# RS485_Demo_Bord_v1_0.net
KiCad netlist of a schematic drawn in Altium Designer
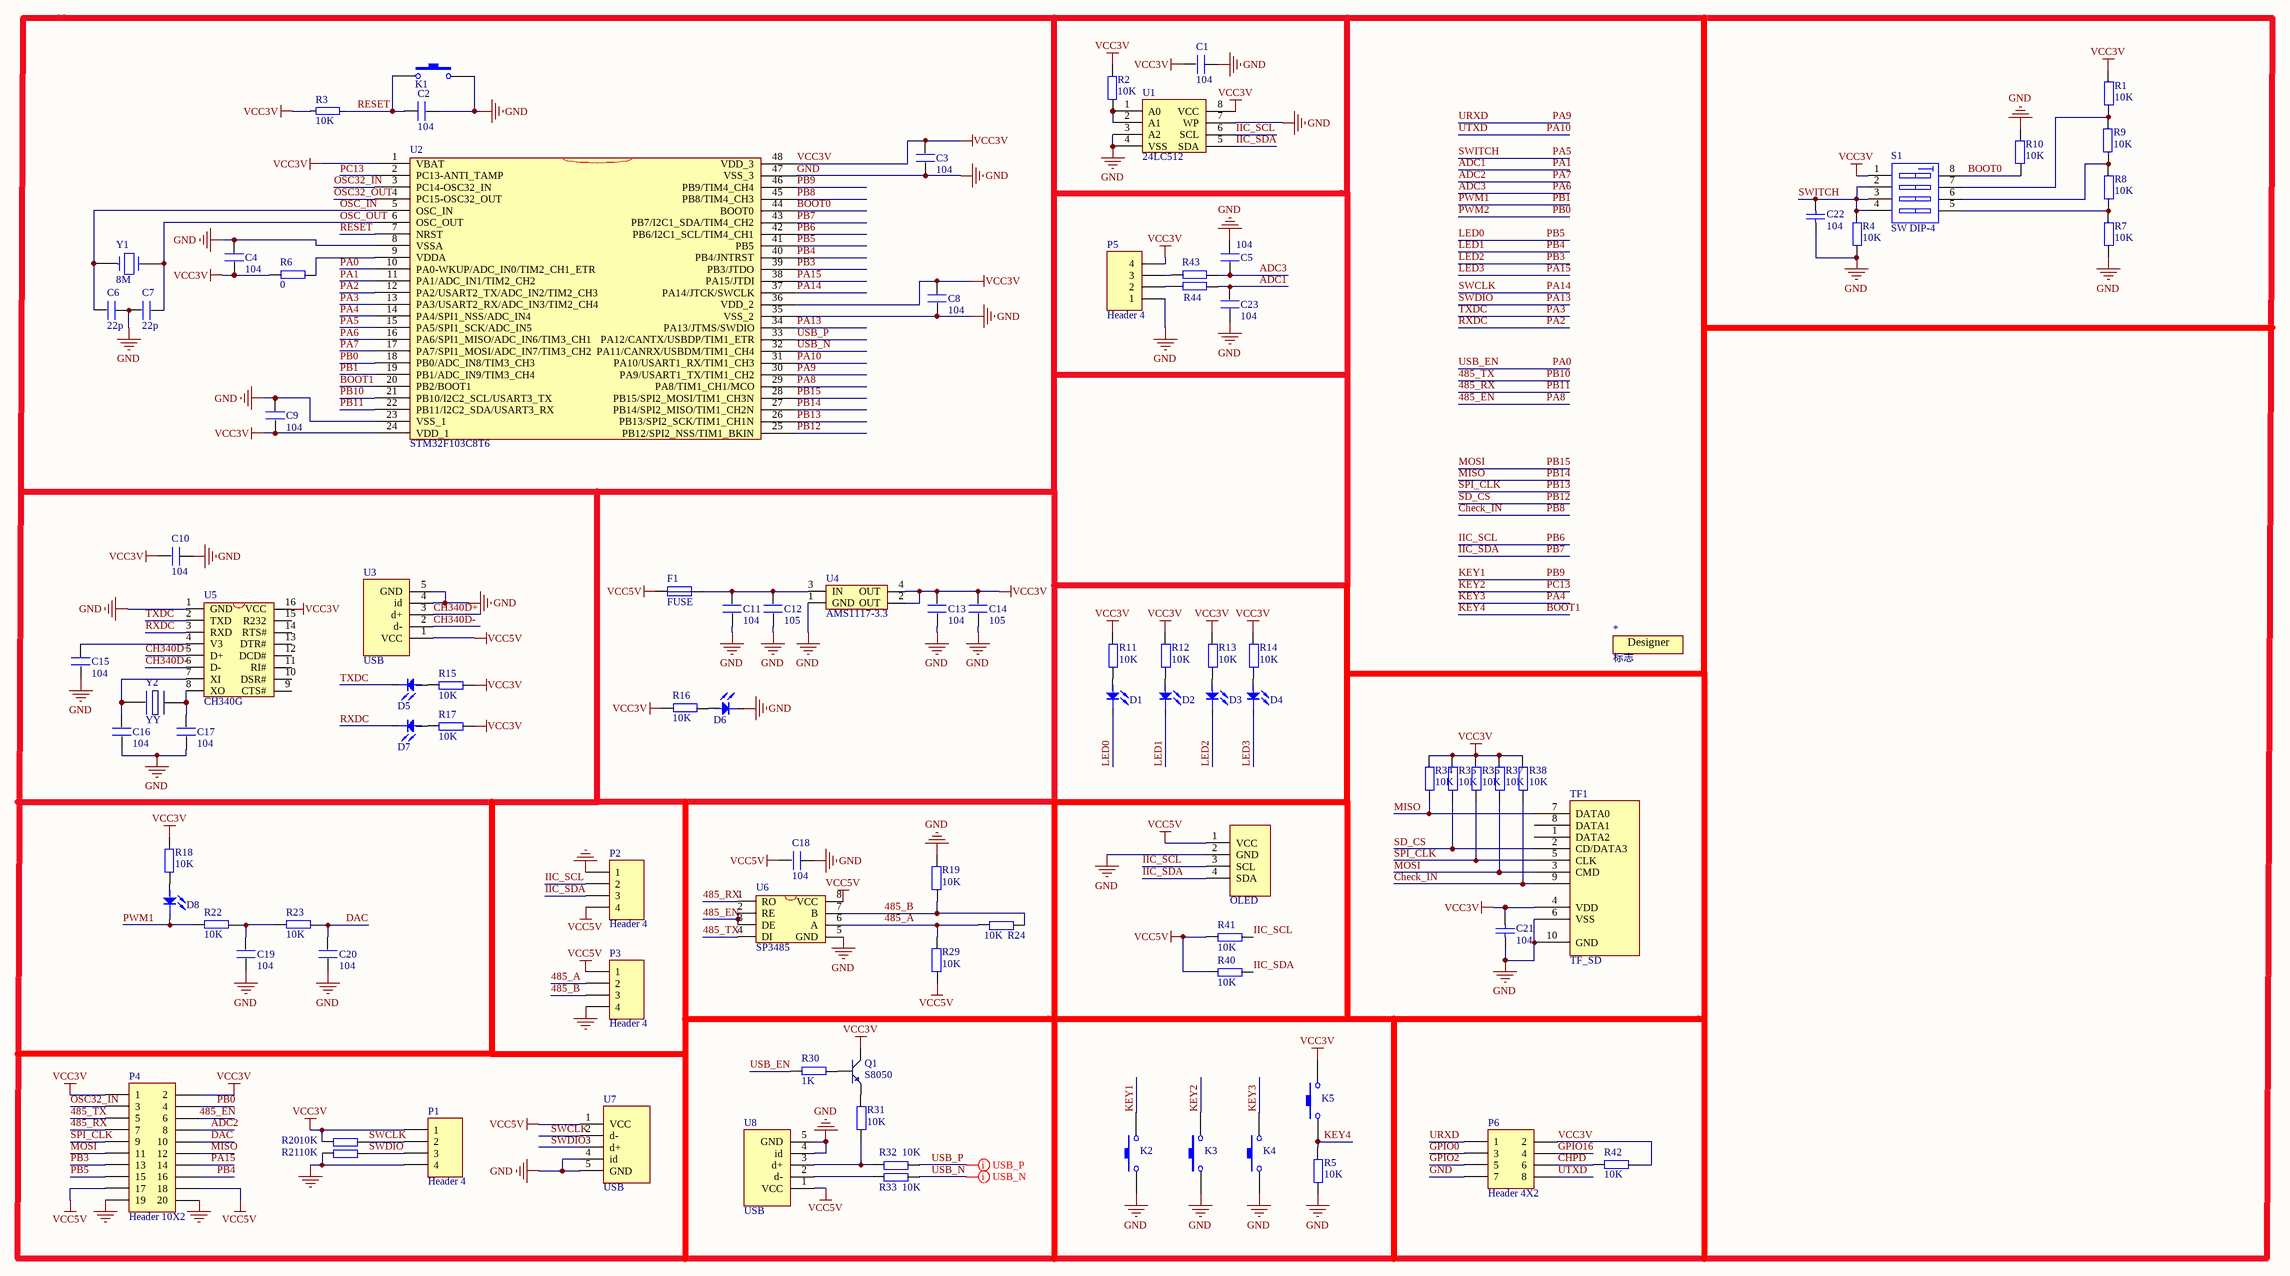
[diagram p0: RS485_Demo_Bord_v1.0.SchDoc]

(export (version "E")
  (design (tool "Eeschema 10.0.6"))
  (components
    (comp (ref "*") (value "标志") (footprint "Designer - 1") (libsource (lib "Mylib") (part "标志")))
    (comp (ref "C1") (value "104") (footprint "C_0805") (libsource (lib "Mylib") (part "C")))
    (comp (ref "C2") (value "104") (footprint "C_0805") (libsource (lib "Mylib") (part "C")))
    (comp (ref "C3") (value "104") (footprint "C_0805") (libsource (lib "Mylib") (part "C")))
    (comp (ref "C4") (value "104") (footprint "C_0805") (libsource (lib "Mylib") (part "C")))
    (comp (ref "C5") (value "104") (footprint "C_0805") (libsource (lib "Mylib") (part "C")))
    (comp (ref "C6") (value "22p") (footprint "C_0805") (libsource (lib "Mylib") (part "C")))
    (comp (ref "C7") (value "22p") (footprint "C_0805") (libsource (lib "Mylib") (part "C")))
    (comp (ref "C8") (value "104") (footprint "C_0805") (libsource (lib "Mylib") (part "C")))
    (comp (ref "C9") (value "104") (footprint "C_0805") (libsource (lib "Mylib") (part "C")))
    (comp (ref "C10") (value "104") (footprint "C_0805") (libsource (lib "Mylib") (part "C")))
    (comp (ref "C11") (value "104") (footprint "C_0805") (libsource (lib "Mylib") (part "C")))
    (comp (ref "C12") (value "105") (footprint "C_0805") (libsource (lib "Mylib") (part "C")))
    (comp (ref "C13") (value "104") (footprint "C_0805") (libsource (lib "Mylib") (part "C")))
    (comp (ref "C14") (value "105") (footprint "C_0805") (libsource (lib "Mylib") (part "C")))
    (comp (ref "C15") (value "104") (footprint "C_0805") (libsource (lib "Mylib") (part "C")))
    (comp (ref "C16") (value "104") (footprint "C_0805") (libsource (lib "Mylib") (part "C")))
    (comp (ref "C17") (value "104") (footprint "C_0805") (libsource (lib "Mylib") (part "C")))
    (comp (ref "C18") (value "104") (footprint "C_0805") (libsource (lib "Mylib") (part "C")))
    (comp (ref "C19") (value "104") (footprint "C_0805") (libsource (lib "Mylib") (part "C")))
    (comp (ref "C20") (value "104") (footprint "C_0805") (libsource (lib "Mylib") (part "C")))
    (comp (ref "C21")
      (value "104")
      (footprint "0805C")
      (description "Capacitor")
      (fields (field (name "PUBLISHER") "Altium Limited"))
      (libsource (lib "STM32F407VET6mini最小系统-原理图库") (part "Cap"))
    )
    (comp (ref "C22")
      (value "104")
      (footprint "0805C")
      (description "Capacitor")
      (fields (field (name "PUBLISHER") "Altium Limited"))
      (libsource (lib "STM32F407VET6mini最小系统-原理图库") (part "Cap"))
    )
    (comp (ref "C23") (value "104") (footprint "C_0805") (libsource (lib "Mylib") (part "C")))
    (comp (ref "D1") (value "LED") (footprint "0805-LED-RED") (libsource (lib "MY SCH LIB") (part "LED")))
    (comp (ref "D2") (value "LED") (footprint "0805-LED-RED") (libsource (lib "MY SCH LIB") (part "LED")))
    (comp (ref "D3") (value "LED") (footprint "0805-LED-RED") (libsource (lib "MY SCH LIB") (part "LED")))
    (comp (ref "D4") (value "LED") (footprint "0805-LED-RED") (libsource (lib "MY SCH LIB") (part "LED")))
    (comp (ref "D5") (value "LED") (footprint "0805-LED-RED") (libsource (lib "MY SCH LIB") (part "LED")))
    (comp (ref "D6") (value "LED") (footprint "0805-LED-RED") (libsource (lib "MY SCH LIB") (part "LED")))
    (comp (ref "D7") (value "LED") (footprint "0805-LED-RED") (libsource (lib "MY SCH LIB") (part "LED")))
    (comp (ref "D8") (value "LED") (footprint "0805-LED-RED") (libsource (lib "MY SCH LIB") (part "LED")))
    (comp (ref "F1") (value "FUSE") (footprint "0805") (libsource (lib "Mylib") (part "FUSE")))
    (comp (ref "K1") (value "KEY") (footprint "KEY_6") (libsource (lib "MY SCH LIB") (part "KEY")))
    (comp (ref "K2") (value "KEY") (footprint "KEY_6") (libsource (lib "MY SCH LIB") (part "KEY")))
    (comp (ref "K3") (value "KEY") (footprint "KEY_6") (libsource (lib "MY SCH LIB") (part "KEY")))
    (comp (ref "K4") (value "KEY") (footprint "KEY_6") (libsource (lib "MY SCH LIB") (part "KEY")))
    (comp (ref "K5") (value "KEY") (footprint "KEY_6") (libsource (lib "MY SCH LIB") (part "KEY")))
    (comp (ref "OLED")
      (value "OLED")
      (footprint "OLED__IIC_1")
      (libsource (lib "MY SCH LIB") (part "OLED_IIC_1"))
    )
    (comp (ref "P1")
      (value "Header 4")
      (footprint "XH_4_V")
      (description "Header, 4-Pin")
      (fields (field (name "PUBLISHER") "Altium Limited"))
      (libsource (lib "") (part "Header 4_1"))
    )
    (comp (ref "P2")
      (value "Header 4")
      (footprint "XH_4_V")
      (description "Header, 4-Pin")
      (fields (field (name "PUBLISHER") "Altium Limited"))
      (libsource (lib "") (part "Header 4_1"))
    )
    (comp (ref "P3")
      (value "Header 4")
      (footprint "XH_4_V")
      (description "Header, 4-Pin")
      (fields (field (name "PUBLISHER") "Altium Limited"))
      (libsource (lib "") (part "Header 4_1"))
    )
    (comp (ref "P4")
      (value "Header 10X2")
      (footprint "JTAG_20 - E")
      (description "Header, 10-Pin, Dual row")
      (fields (field (name "PUBLISHER") "Altium Limited"))
      (libsource (lib "接口插座") (part "Header 10X2"))
    )
    (comp (ref "P5")
      (value "Header 4")
      (footprint "XH_4_V")
      (description "Header, 4-Pin")
      (fields (field (name "PUBLISHER") "Altium Limited"))
      (libsource (lib "接口插座") (part "Header 4"))
    )
    (comp (ref "P6")
      (value "Header 4X2")
      (footprint "HDR2X4")
      (description "Header, 4-Pin, Dual row")
      (fields (field (name "PUBLISHER") "Altium Limited"))
      (libsource (lib "接口插座") (part "Header 4X2"))
    )
    (comp (ref "Q1") (value "S8050") (footprint "SOT23-3") (libsource (lib "Mylib") (part "NPN")))
    (comp (ref "R1") (value "10K") (footprint "0805") (libsource (lib "Mylib") (part "R")))
    (comp (ref "R2") (value "10K") (footprint "0805") (libsource (lib "Mylib") (part "R")))
    (comp (ref "R3") (value "10K") (footprint "0805") (libsource (lib "电阻") (part "RES")))
    (comp (ref "R4") (value "10K") (footprint "0805") (libsource (lib "Mylib") (part "R")))
    (comp (ref "R5") (value "10K") (footprint "0805") (libsource (lib "Mylib") (part "R")))
    (comp (ref "R6") (value "0") (footprint "0805") (libsource (lib "Mylib") (part "R")))
    (comp (ref "R7") (value "10K") (footprint "0805") (libsource (lib "Mylib") (part "R")))
    (comp (ref "R8") (value "10K") (footprint "0805") (libsource (lib "Mylib") (part "R")))
    (comp (ref "R9") (value "10K") (footprint "0805") (libsource (lib "Mylib") (part "R")))
    (comp (ref "R10") (value "10K") (footprint "0805") (libsource (lib "Mylib") (part "R")))
    (comp (ref "R11") (value "10K") (footprint "0805") (libsource (lib "Mylib") (part "R")))
    (comp (ref "R12") (value "10K") (footprint "0805") (libsource (lib "Mylib") (part "R")))
    (comp (ref "R13") (value "10K") (footprint "0805") (libsource (lib "Mylib") (part "R")))
    (comp (ref "R14") (value "10K") (footprint "0805") (libsource (lib "Mylib") (part "R")))
    (comp (ref "R15") (value "10K") (footprint "0805") (libsource (lib "Mylib") (part "R")))
    (comp (ref "R16") (value "10K") (footprint "0805") (libsource (lib "Mylib") (part "R")))
    (comp (ref "R17") (value "10K") (footprint "0805") (libsource (lib "Mylib") (part "R")))
    (comp (ref "R18") (value "10K") (footprint "0805") (libsource (lib "Mylib") (part "R")))
    (comp (ref "R19") (value "10K") (footprint "0805") (libsource (lib "Mylib") (part "R")))
    (comp (ref "R20") (value "10K") (footprint "0805") (libsource (lib "Mylib") (part "R")))
    (comp (ref "R21") (value "10K") (footprint "0805") (libsource (lib "Mylib") (part "R")))
    (comp (ref "R22") (value "10K") (footprint "0805") (libsource (lib "Mylib") (part "R")))
    (comp (ref "R23") (value "10K") (footprint "0805") (libsource (lib "Mylib") (part "R")))
    (comp (ref "R24") (value "10K") (footprint "0805") (libsource (lib "Mylib") (part "R")))
    (comp (ref "R29") (value "10K") (footprint "0805") (libsource (lib "Mylib") (part "R")))
    (comp (ref "R30") (value "1K") (footprint "0805") (libsource (lib "Mylib") (part "R")))
    (comp (ref "R31") (value "10K") (footprint "0805") (libsource (lib "Mylib") (part "R")))
    (comp (ref "R32") (value "10K") (footprint "0805") (libsource (lib "Mylib") (part "R")))
    (comp (ref "R33") (value "10K") (footprint "0805") (libsource (lib "Mylib") (part "R")))
    (comp (ref "R34") (value "10K") (footprint "0805") (libsource (lib "Mylib") (part "R")))
    (comp (ref "R35") (value "10K") (footprint "0805") (libsource (lib "Mylib") (part "R")))
    (comp (ref "R36") (value "10K") (footprint "0805") (libsource (lib "Mylib") (part "R")))
    (comp (ref "R37") (value "10K") (footprint "0805") (libsource (lib "Mylib") (part "R")))
    (comp (ref "R38") (value "10K") (footprint "0805") (libsource (lib "Mylib") (part "R")))
    (comp (ref "R40") (value "10K") (footprint "0805") (libsource (lib "Mylib") (part "R")))
    (comp (ref "R41") (value "10K") (footprint "0805") (libsource (lib "Mylib") (part "R")))
    (comp (ref "R42") (value "10K") (footprint "0805") (libsource (lib "Mylib") (part "R")))
    (comp (ref "R43") (value "10K") (footprint "0805") (libsource (lib "Mylib") (part "R")))
    (comp (ref "R44") (value "10K") (footprint "0805") (libsource (lib "Mylib") (part "R")))
    (comp (ref "S1")
      (value "SW DIP-4")
      (footprint "SWITCH_DIP-4")
      (description "DIP Switch")
      (libsource (lib "MY SCH LIB") (part "SW DIP-4"))
    )
    (comp (ref "TF1") (value "TF_SD") (footprint "TF_SD") (libsource (lib "stm32f103vet6") (part "TF_SD")))
    (comp (ref "U1") (value "24LC512") (footprint "SO-8") (libsource (lib "Mylib") (part "24LC512")))
    (comp (ref "U2")
      (value "STM32F103C8T6")
      (footprint "LQFP-48_M")
      (libsource (lib "stm32") (part "STM32F103C6"))
    )
    (comp (ref "U3") (value "USB") (footprint "USB_MICRO_F") (libsource (lib "") (part "USB_1")))
    (comp (ref "U4")
      (value "AMS1117-3.3")
      (footprint "SOT223")
      (libsource (lib "MY SCH LIB") (part "AMS1117"))
    )
    (comp (ref "U5") (value "CH340G") (footprint "SO-16") (libsource (lib "Mylib") (part "CH340G")))
    (comp (ref "U6")
      (value "SP3485")
      (footprint "SOP-8")
      (libsource (lib "战舰STM32开发板底板封装库") (part "MAX3485"))
    )
    (comp (ref "U7") (value "USB") (footprint "USB_MICRO_F") (libsource (lib "MY SCH LIB") (part "USB")))
    (comp (ref "U8") (value "USB") (footprint "USB_MICRO_F") (libsource (lib "") (part "USB_1")))
    (comp (ref "Y1")
      (value "8M")
      (footprint "XTAL-3")
      (description "Crystal")
      (libsource (lib "MY SCH LIB") (part "CRYSTAL"))
    )
    (comp (ref "Y2") (value "YY") (footprint "XTAL-3") (libsource (lib "Mylib") (part "YY")))
  )
  (nets
    (net (code "1") (name "/485_A") (class "Default")
      (node (ref "P3") (pin "2") (pinfunction "2_2") (pintype "passive"))
      (node (ref "R24") (pin "1") (pintype "passive"))
      (node (ref "R29") (pin "1") (pintype "passive"))
      (node (ref "U6") (pin "6") (pinfunction "A_6") (pintype "passive"))
    )
    (net (code "2") (name "/485_B") (class "Default")
      (node (ref "P3") (pin "3") (pinfunction "3_3") (pintype "passive"))
      (node (ref "R19") (pin "2") (pintype "passive"))
      (node (ref "R24") (pin "2") (pintype "passive"))
      (node (ref "U6") (pin "7") (pinfunction "B_7") (pintype "passive"))
    )
    (net (code "3") (name "/485_EN") (class "Default")
      (node (ref "P4") (pin "6") (pinfunction "6_6") (pintype "passive"))
      (node (ref "U2") (pin "29") (pinfunction "PA8/TIM1_CH1/MCO_29") (pintype "passive"))
      (node (ref "U6") (pin "2") (pinfunction "RE_2") (pintype "passive"))
      (node (ref "U6") (pin "3") (pinfunction "DE_3") (pintype "passive"))
    )
    (net (code "4") (name "/485_RX") (class "Default")
      (node (ref "P4") (pin "7") (pinfunction "7_7") (pintype "passive"))
      (node (ref "U2") (pin "22") (pinfunction "PB11/I2C2_SDA/USART3_RX_22") (pintype "passive"))
      (node (ref "U6") (pin "1") (pinfunction "RO_1") (pintype "passive"))
    )
    (net (code "5") (name "/485_TX") (class "Default")
      (node (ref "P4") (pin "5") (pinfunction "5_5") (pintype "passive"))
      (node (ref "U2") (pin "21") (pinfunction "PB10/I2C2_SCL/USART3_TX_21") (pintype "passive"))
      (node (ref "U6") (pin "4") (pinfunction "DI_4") (pintype "passive"))
    )
    (net (code "6") (name "/ADC1") (class "Default")
      (node (ref "C23") (pin "2") (pintype "passive"))
      (node (ref "R44") (pin "1") (pintype "passive"))
      (node (ref "U2") (pin "11") (pinfunction "PA1/ADC_IN1/TIM2_CH2_11") (pintype "passive"))
    )
    (net (code "7") (name "/ADC2") (class "Default")
      (node (ref "P4") (pin "8") (pinfunction "8_8") (pintype "passive"))
      (node (ref "U2") (pin "17") (pinfunction "PA7/SPI1_MOSI/ADC_IN7/TIM3_CH2_17") (pintype "passive"))
    )
    (net (code "8") (name "/ADC3") (class "Default")
      (node (ref "C5") (pin "1") (pintype "passive"))
      (node (ref "R43") (pin "1") (pintype "passive"))
      (node (ref "U2") (pin "16") (pinfunction "PA6/SPI1_MISO/ADC_IN6/TIM3_CH1_16") (pintype "passive"))
    )
    (net (code "9") (name "/BOOT0") (class "Default")
      (node (ref "R10") (pin "2") (pintype "passive"))
      (node (ref "S1") (pin "8") (pinfunction "B1_8") (pintype "passive"))
      (node (ref "U2") (pin "44") (pinfunction "BOOT0_44") (pintype "passive"))
    )
    (net (code "10") (name "/BOOT1") (class "Default")
      (node (ref "K5") (pin "1") (pinfunction "1_1") (pintype "passive"))
      (node (ref "R5") (pin "2") (pintype "passive"))
      (node (ref "U2") (pin "20") (pinfunction "PB2/BOOT1_20") (pintype "passive"))
    )
    (net (code "11") (name "/CH340D+") (class "Default")
      (node (ref "U3") (pin "3") (pinfunction "d+_3") (pintype "passive"))
      (node (ref "U5") (pin "5") (pinfunction "D+_5") (pintype "passive"))
    )
    (net (code "12") (name "/CH340D-") (class "Default")
      (node (ref "U3") (pin "2") (pinfunction "d-_2") (pintype "passive"))
      (node (ref "U5") (pin "6") (pinfunction "D-_6") (pintype "passive"))
    )
    (net (code "13") (name "/CHPD") (class "Default")
      (node (ref "P6") (pin "6") (pinfunction "6_6") (pintype "passive"))
      (node (ref "R42") (pin "2") (pintype "passive"))
    )
    (net (code "14") (name "/Check_IN") (class "Default")
      (node (ref "R38") (pin "1") (pintype "passive"))
      (node (ref "TF1") (pin "9") (pinfunction "VSS_9") (pintype "passive"))
      (node (ref "U2") (pin "45") (pinfunction "PB8/TIM4_CH3_45") (pintype "passive"))
    )
    (net (code "15") (name "/DAC") (class "Default")
      (node (ref "C20") (pin "2") (pintype "passive"))
      (node (ref "P4") (pin "10") (pinfunction "10_10") (pintype "passive"))
      (node (ref "R23") (pin "1") (pintype "passive"))
    )
    (net (code "16") (name "/GPIO0") (class "Default")
      (node (ref "P6") (pin "3") (pinfunction "3_3") (pintype "passive"))
    )
    (net (code "17") (name "/GPIO2") (class "Default")
      (node (ref "P6") (pin "5") (pinfunction "5_5") (pintype "passive"))
    )
    (net (code "18") (name "/GPIO16") (class "Default")
      (node (ref "P6") (pin "4") (pinfunction "4_4") (pintype "passive"))
    )
    (net (code "19") (name "/IIC_SCL") (class "Default")
      (node (ref "OLED") (pin "3") (pinfunction "SCL_3") (pintype "passive"))
      (node (ref "P2") (pin "2") (pinfunction "2_2") (pintype "passive"))
      (node (ref "R41") (pin "2") (pintype "passive"))
      (node (ref "U1") (pin "6") (pinfunction "SCL_6") (pintype "passive"))
      (node (ref "U2") (pin "42") (pinfunction "PB6/I2C1_SCL/TIM4_CH1_42") (pintype "passive"))
    )
    (net (code "20") (name "/IIC_SDA") (class "Default")
      (node (ref "OLED") (pin "4") (pinfunction "SDA_4") (pintype "passive"))
      (node (ref "P2") (pin "3") (pinfunction "3_3") (pintype "passive"))
      (node (ref "R40") (pin "2") (pintype "passive"))
      (node (ref "U1") (pin "5") (pinfunction "SDA_5") (pintype "passive"))
      (node (ref "U2") (pin "43") (pinfunction "PB7/I2C1_SDA/TIM4_CH2_43") (pintype "passive"))
    )
    (net (code "21") (name "/KEY1") (class "Default")
      (node (ref "K2") (pin "2") (pinfunction "2_2") (pintype "passive"))
      (node (ref "U2") (pin "46") (pinfunction "PB9/TIM4_CH4_46") (pintype "passive"))
    )
    (net (code "22") (name "/KEY2") (class "Default")
      (node (ref "K3") (pin "2") (pinfunction "2_2") (pintype "passive"))
      (node (ref "U2") (pin "2") (pinfunction "PC13-ANTI_TAMP_2") (pintype "passive"))
    )
    (net (code "23") (name "/KEY3") (class "Default")
      (node (ref "K4") (pin "2") (pinfunction "2_2") (pintype "passive"))
      (node (ref "U2") (pin "14") (pinfunction "PA4/SPI1_NSS/ADC_IN4_14") (pintype "passive"))
    )
    (net (code "24") (name "/LED0") (class "Default")
      (node (ref "D1") (pin "K") (pintype "passive"))
      (node (ref "P4") (pin "15") (pinfunction "15_15") (pintype "passive"))
      (node (ref "U2") (pin "41") (pinfunction "PB5_41") (pintype "passive"))
    )
    (net (code "25") (name "/LED1") (class "Default")
      (node (ref "D2") (pin "K") (pintype "passive"))
      (node (ref "P4") (pin "16") (pinfunction "16_16") (pintype "passive"))
      (node (ref "U2") (pin "40") (pinfunction "PB4/JNTRST_40") (pintype "passive"))
    )
    (net (code "26") (name "/LED2") (class "Default")
      (node (ref "D3") (pin "K") (pintype "passive"))
      (node (ref "P4") (pin "13") (pinfunction "13_13") (pintype "passive"))
      (node (ref "U2") (pin "39") (pinfunction "PB3/JTDO_39") (pintype "passive"))
    )
    (net (code "27") (name "/LED3") (class "Default")
      (node (ref "D4") (pin "K") (pintype "passive"))
      (node (ref "P4") (pin "14") (pinfunction "14_14") (pintype "passive"))
      (node (ref "U2") (pin "38") (pinfunction "PA15/JTDI_38") (pintype "passive"))
    )
    (net (code "28") (name "/MISO") (class "Default")
      (node (ref "P4") (pin "12") (pinfunction "12_12") (pintype "passive"))
      (node (ref "R34") (pin "1") (pintype "passive"))
      (node (ref "TF1") (pin "7") (pinfunction "DATA0_7") (pintype "passive"))
      (node (ref "U2") (pin "27") (pinfunction "PB14/SPI2_MISO/TIM1_CH2N_27") (pintype "passive"))
    )
    (net (code "29") (name "/MOSI") (class "Default")
      (node (ref "P4") (pin "11") (pinfunction "11_11") (pintype "passive"))
      (node (ref "R37") (pin "1") (pintype "passive"))
      (node (ref "TF1") (pin "3") (pinfunction "CMD_3") (pintype "passive"))
      (node (ref "U2") (pin "28") (pinfunction "PB15/SPI2_MOSI/TIM1_CH3N_28") (pintype "passive"))
    )
    (net (code "30") (name "/OSC32_IN") (class "Default")
      (node (ref "P4") (pin "3") (pinfunction "3_3") (pintype "passive"))
      (node (ref "U2") (pin "3") (pinfunction "PC14-OSC32_IN_3") (pintype "passive"))
    )
    (net (code "31") (name "/OSC32_OUT") (class "Default")
      (node (ref "U2") (pin "4") (pinfunction "PC15-OSC32_OUT_4") (pintype "passive"))
    )
    (net (code "32") (name "/OSC_IN") (class "Default")
      (node (ref "C6") (pin "2") (pintype "passive"))
      (node (ref "U2") (pin "5") (pinfunction "OSC_IN_5") (pintype "passive"))
      (node (ref "Y1") (pin "1") (pinfunction "1_1") (pintype "passive"))
    )
    (net (code "33") (name "/OSC_OUT") (class "Default")
      (node (ref "C7") (pin "1") (pintype "passive"))
      (node (ref "U2") (pin "6") (pinfunction "OSC_OUT_6") (pintype "passive"))
      (node (ref "Y1") (pin "2") (pinfunction "2_2") (pintype "passive"))
    )
    (net (code "34") (name "/PA0") (class "Default")
      (node (ref "R30") (pin "2") (pintype "passive"))
      (node (ref "U2") (pin "10") (pinfunction "PA0-WKUP/ADC_IN0/TIM2_CH1_ETR_10") (pintype "passive"))
    )
    (net (code "35") (name "/PA2") (class "Default")
      (node (ref "D7") (pin "K") (pintype "passive"))
      (node (ref "U2") (pin "12") (pinfunction "PA2/USART2_TX/ADC_IN2/TIM2_CH3_12") (pintype "passive"))
      (node (ref "U5") (pin "3") (pinfunction "RXD_3") (pintype "passive"))
    )
    (net (code "36") (name "/PA3") (class "Default")
      (node (ref "D5") (pin "K") (pintype "passive"))
      (node (ref "U2") (pin "13") (pinfunction "PA3/USART2_RX/ADC_IN3/TIM2_CH4_13") (pintype "passive"))
      (node (ref "U5") (pin "2") (pinfunction "TXD_2") (pintype "passive"))
    )
    (net (code "37") (name "/PA5") (class "Default")
      (node (ref "C22") (pin "2") (pinfunction "2_2") (pintype "passive"))
      (node (ref "R4") (pin "2") (pintype "passive"))
      (node (ref "S1") (pin "2") (pinfunction "A2_2") (pintype "passive"))
      (node (ref "S1") (pin "3") (pinfunction "A3_3") (pintype "passive"))
      (node (ref "S1") (pin "4") (pinfunction "A4_4") (pintype "passive"))
      (node (ref "U2") (pin "15") (pinfunction "PA5/SPI1_SCK/ADC_IN5_15") (pintype "passive"))
    )
    (net (code "38") (name "/PA9") (class "Default")
      (node (ref "P6") (pin "1") (pinfunction "1_1") (pintype "passive"))
      (node (ref "U2") (pin "30") (pinfunction "PA9/USART1_TX/TIM1_CH2_30") (pintype "passive"))
    )
    (net (code "39") (name "/PA10") (class "Default")
      (node (ref "P6") (pin "8") (pinfunction "8_8") (pintype "passive"))
      (node (ref "U2") (pin "31") (pinfunction "PA10/USART1_RX/TIM1_CH3_31") (pintype "passive"))
    )
    (net (code "40") (name "/PA13") (class "Default")
      (node (ref "P1") (pin "3") (pinfunction "3_3") (pintype "passive"))
      (node (ref "R21") (pin "2") (pintype "passive"))
      (node (ref "U2") (pin "34") (pinfunction "PA13/JTMS/SWDIO_34") (pintype "passive"))
      (node (ref "U7") (pin "3") (pinfunction "d+_3") (pintype "passive"))
    )
    (net (code "41") (name "/PA14") (class "Default")
      (node (ref "P1") (pin "2") (pinfunction "2_2") (pintype "passive"))
      (node (ref "R20") (pin "2") (pintype "passive"))
      (node (ref "U2") (pin "37") (pinfunction "PA14/JTCK/SWCLK_37") (pintype "passive"))
      (node (ref "U7") (pin "2") (pinfunction "d-_2") (pintype "passive"))
    )
    (net (code "42") (name "/PB0") (class "Default")
      (node (ref "P4") (pin "4") (pinfunction "4_4") (pintype "passive"))
      (node (ref "U2") (pin "18") (pinfunction "PB0/ADC_IN8/TIM3_CH3_18") (pintype "passive"))
    )
    (net (code "43") (name "/PB1") (class "Default")
      (node (ref "D8") (pin "K") (pintype "passive"))
      (node (ref "R22") (pin "2") (pintype "passive"))
      (node (ref "U2") (pin "19") (pinfunction "PB1/ADC_IN9/TIM3_CH4_19") (pintype "passive"))
    )
    (net (code "44") (name "/PB12") (class "Default")
      (node (ref "R35") (pin "1") (pintype "passive"))
      (node (ref "TF1") (pin "2") (pinfunction "CD/DATA3_2") (pintype "passive"))
      (node (ref "U2") (pin "25") (pinfunction "PB12/SPI2_NSS/TIM1_BKIN_25") (pintype "passive"))
    )
    (net (code "45") (name "/PB13") (class "Default")
      (node (ref "P4") (pin "9") (pinfunction "9_9") (pintype "passive"))
      (node (ref "R36") (pin "1") (pintype "passive"))
      (node (ref "TF1") (pin "5") (pinfunction "CLK_5") (pintype "passive"))
      (node (ref "U2") (pin "26") (pinfunction "PB13/SPI2_SCK/TIM1_CH1N_26") (pintype "passive"))
    )
    (net (code "46") (name "/RESET") (class "Default")
      (node (ref "C2") (pin "1") (pintype "passive"))
      (node (ref "K1") (pin "1") (pinfunction "1_1") (pintype "passive"))
      (node (ref "R3") (pin "1") (pinfunction "1_1") (pintype "passive"))
      (node (ref "U2") (pin "7") (pinfunction "NRST_7") (pintype "passive"))
    )
    (net (code "47") (name "/USB_N") (class "Default")
      (node (ref "R33") (pin "2") (pintype "passive"))
      (node (ref "U2") (pin "32") (pinfunction "PA11/CANRX/USBDM/TIM1_CH4_32") (pintype "passive"))
    )
    (net (code "48") (name "/USB_P") (class "Default")
      (node (ref "R32") (pin "2") (pintype "passive"))
      (node (ref "U2") (pin "33") (pinfunction "PA12/CANTX/USBDP/TIM1_ETR_33") (pintype "passive"))
    )
    (net (code "49") (name "GND") (class "Default")
      (node (ref "C1") (pin "1") (pintype "passive"))
      (node (ref "C10") (pin "1") (pintype "passive"))
      (node (ref "C11") (pin "1") (pintype "passive"))
      (node (ref "C12") (pin "1") (pintype "passive"))
      (node (ref "C13") (pin "1") (pintype "passive"))
      (node (ref "C14") (pin "1") (pintype "passive"))
      (node (ref "C15") (pin "1") (pintype "passive"))
      (node (ref "C16") (pin "1") (pintype "passive"))
      (node (ref "C17") (pin "1") (pintype "passive"))
      (node (ref "C18") (pin "1") (pintype "passive"))
      (node (ref "C19") (pin "1") (pintype "passive"))
      (node (ref "C2") (pin "2") (pintype "passive"))
      (node (ref "C20") (pin "1") (pintype "passive"))
      (node (ref "C21") (pin "1") (pinfunction "1_1") (pintype "passive"))
      (node (ref "C22") (pin "1") (pinfunction "1_1") (pintype "passive"))
      (node (ref "C23") (pin "1") (pintype "passive"))
      (node (ref "C3") (pin "1") (pintype "passive"))
      (node (ref "C4") (pin "2") (pintype "passive"))
      (node (ref "C5") (pin "2") (pintype "passive"))
      (node (ref "C6") (pin "1") (pintype "passive"))
      (node (ref "C7") (pin "2") (pintype "passive"))
      (node (ref "C8") (pin "1") (pintype "passive"))
      (node (ref "C9") (pin "2") (pintype "passive"))
      (node (ref "D6") (pin "K") (pintype "passive"))
      (node (ref "K1") (pin "2") (pinfunction "2_2") (pintype "passive"))
      (node (ref "K2") (pin "1") (pinfunction "1_1") (pintype "passive"))
      (node (ref "K3") (pin "1") (pinfunction "1_1") (pintype "passive"))
      (node (ref "K4") (pin "1") (pinfunction "1_1") (pintype "passive"))
      (node (ref "OLED") (pin "2") (pinfunction "GND_2") (pintype "passive"))
      (node (ref "P1") (pin "4") (pinfunction "4_4") (pintype "passive"))
      (node (ref "P2") (pin "1") (pinfunction "1_1") (pintype "passive"))
      (node (ref "P3") (pin "4") (pinfunction "4_4") (pintype "passive"))
      (node (ref "P4") (pin "19") (pinfunction "19_19") (pintype "passive"))
      (node (ref "P4") (pin "20") (pinfunction "20_20") (pintype "passive"))
      (node (ref "P5") (pin "1") (pinfunction "1_1") (pintype "passive"))
      (node (ref "P6") (pin "7") (pinfunction "7_7") (pintype "passive"))
      (node (ref "R10") (pin "1") (pintype "passive"))
      (node (ref "R19") (pin "1") (pintype "passive"))
      (node (ref "R21") (pin "1") (pintype "passive"))
      (node (ref "R4") (pin "1") (pintype "passive"))
      (node (ref "R5") (pin "1") (pintype "passive"))
      (node (ref "R7") (pin "1") (pintype "passive"))
      (node (ref "TF1") (pin "10") (pinfunction "GND_10") (pintype "passive"))
      (node (ref "TF1") (pin "6") (pinfunction "VSS_6") (pintype "passive"))
      (node (ref "U1") (pin "3") (pinfunction "A2_3") (pintype "passive"))
      (node (ref "U1") (pin "4") (pinfunction "VSS_4") (pintype "passive"))
      (node (ref "U1") (pin "7") (pinfunction "WP_7") (pintype "passive"))
      (node (ref "U2") (pin "23") (pinfunction "VSS_1_23") (pintype "passive"))
      (node (ref "U2") (pin "35") (pinfunction "VSS_2_35") (pintype "passive"))
      (node (ref "U2") (pin "47") (pinfunction "VSS_3_47") (pintype "passive"))
      (node (ref "U2") (pin "8") (pinfunction "VSSA_8") (pintype "passive"))
      (node (ref "U3") (pin "4") (pinfunction "id_4") (pintype "passive"))
      (node (ref "U3") (pin "5") (pinfunction "GND_5") (pintype "passive"))
      (node (ref "U4") (pin "1") (pinfunction "GND_1") (pintype "passive"))
      (node (ref "U5") (pin "1") (pinfunction "GND_1") (pintype "passive"))
      (node (ref "U6") (pin "5") (pinfunction "GND_5") (pintype "passive"))
      (node (ref "U7") (pin "4") (pinfunction "id_4") (pintype "passive"))
      (node (ref "U7") (pin "5") (pinfunction "GND_5") (pintype "passive"))
      (node (ref "U8") (pin "4") (pinfunction "id_4") (pintype "passive"))
      (node (ref "U8") (pin "5") (pinfunction "GND_5") (pintype "passive"))
    )
    (net (code "50") (name "Net-(C19-Pad2)") (class "Default")
      (node (ref "C19") (pin "2") (pintype "passive"))
      (node (ref "R22") (pin "1") (pintype "passive"))
      (node (ref "R23") (pin "2") (pintype "passive"))
    )
    (net (code "51") (name "Net-(D1-PadA)") (class "Default")
      (node (ref "D1") (pin "A") (pintype "passive"))
      (node (ref "R11") (pin "1") (pintype "passive"))
    )
    (net (code "52") (name "Net-(D2-PadA)") (class "Default")
      (node (ref "D2") (pin "A") (pintype "passive"))
      (node (ref "R12") (pin "1") (pintype "passive"))
    )
    (net (code "53") (name "Net-(D3-PadA)") (class "Default")
      (node (ref "D3") (pin "A") (pintype "passive"))
      (node (ref "R13") (pin "1") (pintype "passive"))
    )
    (net (code "54") (name "Net-(D4-PadA)") (class "Default")
      (node (ref "D4") (pin "A") (pintype "passive"))
      (node (ref "R14") (pin "1") (pintype "passive"))
    )
    (net (code "55") (name "Net-(D5-PadA)") (class "Default")
      (node (ref "D5") (pin "A") (pintype "passive"))
      (node (ref "R15") (pin "1") (pintype "passive"))
    )
    (net (code "56") (name "Net-(D6-PadA)") (class "Default")
      (node (ref "D6") (pin "A") (pintype "passive"))
      (node (ref "R16") (pin "1") (pintype "passive"))
    )
    (net (code "57") (name "Net-(D7-PadA)") (class "Default")
      (node (ref "D7") (pin "A") (pintype "passive"))
      (node (ref "R17") (pin "1") (pintype "passive"))
    )
    (net (code "58") (name "Net-(D8-PadA)") (class "Default")
      (node (ref "D8") (pin "A") (pintype "passive"))
      (node (ref "R18") (pin "2") (pintype "passive"))
    )
    (net (code "59") (name "Net-(P5-Pad2)") (class "Default")
      (node (ref "P5") (pin "2") (pinfunction "2_2") (pintype "passive"))
      (node (ref "R44") (pin "2") (pintype "passive"))
    )
    (net (code "60") (name "Net-(P5-Pad3)") (class "Default")
      (node (ref "P5") (pin "3") (pinfunction "3_3") (pintype "passive"))
      (node (ref "R43") (pin "2") (pintype "passive"))
    )
    (net (code "61") (name "Net-(Q1-B)") (class "Default")
      (node (ref "Q1") (pin "1") (pinfunction "B_1") (pintype "passive"))
      (node (ref "R30") (pin "1") (pintype "passive"))
    )
    (net (code "62") (name "Net-(Q1-E)") (class "Default")
      (node (ref "Q1") (pin "3") (pinfunction "E_3") (pintype "passive"))
      (node (ref "R31") (pin "2") (pintype "passive"))
    )
    (net (code "63") (name "Net-(S1-B2)") (class "Default")
      (node (ref "R1") (pin "1") (pintype "passive"))
      (node (ref "R9") (pin "1") (pintype "passive"))
      (node (ref "S1") (pin "7") (pinfunction "B2_7") (pintype "passive"))
    )
    (net (code "64") (name "Net-(S1-B3)") (class "Default")
      (node (ref "R8") (pin "2") (pintype "passive"))
      (node (ref "R9") (pin "2") (pintype "passive"))
      (node (ref "S1") (pin "6") (pinfunction "B3_6") (pintype "passive"))
    )
    (net (code "65") (name "Net-(S1-B4)") (class "Default")
      (node (ref "R7") (pin "2") (pintype "passive"))
      (node (ref "R8") (pin "1") (pintype "passive"))
      (node (ref "S1") (pin "5") (pinfunction "B4_5") (pintype "passive"))
    )
    (net (code "66") (name "Net-(U1-A0)") (class "Default")
      (node (ref "R2") (pin "2") (pintype "passive"))
      (node (ref "U1") (pin "1") (pinfunction "A0_1") (pintype "passive"))
      (node (ref "U1") (pin "2") (pinfunction "A1_2") (pintype "passive"))
    )
    (net (code "67") (name "Net-(U2-VDDA)") (class "Default")
      (node (ref "R6") (pin "1") (pintype "passive"))
      (node (ref "U2") (pin "9") (pinfunction "VDDA_9") (pintype "passive"))
    )
    (net (code "68") (name "Net-(U4-IN)") (class "Default")
      (node (ref "C11") (pin "2") (pintype "passive"))
      (node (ref "C12") (pin "2") (pintype "passive"))
      (node (ref "F1") (pin "2") (pintype "passive"))
      (node (ref "U4") (pin "3") (pinfunction "IN_3") (pintype "passive"))
    )
    (net (code "69") (name "Net-(U5-V3)") (class "Default")
      (node (ref "C15") (pin "2") (pintype "passive"))
      (node (ref "U5") (pin "4") (pinfunction "V3_4") (pintype "passive"))
    )
    (net (code "70") (name "Net-(U5-XI)") (class "Default")
      (node (ref "C16") (pin "2") (pintype "passive"))
      (node (ref "U5") (pin "7") (pinfunction "XI_7") (pintype "passive"))
      (node (ref "Y2") (pin "2") (pintype "passive"))
    )
    (net (code "71") (name "Net-(U5-XO)") (class "Default")
      (node (ref "C17") (pin "2") (pintype "passive"))
      (node (ref "U5") (pin "8") (pinfunction "XO_8") (pintype "passive"))
      (node (ref "Y2") (pin "1") (pintype "passive"))
    )
    (net (code "72") (name "Net-(U8-d+)") (class "Default")
      (node (ref "R31") (pin "1") (pintype "passive"))
      (node (ref "R32") (pin "1") (pintype "passive"))
      (node (ref "U8") (pin "3") (pinfunction "d+_3") (pintype "passive"))
    )
    (net (code "73") (name "Net-(U8-d-)") (class "Default")
      (node (ref "R33") (pin "1") (pintype "passive"))
      (node (ref "U8") (pin "2") (pinfunction "d-_2") (pintype "passive"))
    )
    (net (code "74") (name "VCC3V") (class "Default")
      (node (ref "C1") (pin "2") (pintype "passive"))
      (node (ref "C10") (pin "2") (pintype "passive"))
      (node (ref "C13") (pin "2") (pintype "passive"))
      (node (ref "C14") (pin "2") (pintype "passive"))
      (node (ref "C21") (pin "2") (pinfunction "2_2") (pintype "passive"))
      (node (ref "C3") (pin "2") (pintype "passive"))
      (node (ref "C4") (pin "1") (pintype "passive"))
      (node (ref "C8") (pin "2") (pintype "passive"))
      (node (ref "C9") (pin "1") (pintype "passive"))
      (node (ref "K5") (pin "2") (pinfunction "2_2") (pintype "passive"))
      (node (ref "P1") (pin "1") (pinfunction "1_1") (pintype "passive"))
      (node (ref "P4") (pin "1") (pinfunction "1_1") (pintype "passive"))
      (node (ref "P4") (pin "2") (pinfunction "2_2") (pintype "passive"))
      (node (ref "P5") (pin "4") (pinfunction "4_4") (pintype "passive"))
      (node (ref "P6") (pin "2") (pinfunction "2_2") (pintype "passive"))
      (node (ref "Q1") (pin "2") (pinfunction "C_2") (pintype "passive"))
      (node (ref "R1") (pin "2") (pintype "passive"))
      (node (ref "R11") (pin "2") (pintype "passive"))
      (node (ref "R12") (pin "2") (pintype "passive"))
      (node (ref "R13") (pin "2") (pintype "passive"))
      (node (ref "R14") (pin "2") (pintype "passive"))
      (node (ref "R15") (pin "2") (pintype "passive"))
      (node (ref "R16") (pin "2") (pintype "passive"))
      (node (ref "R17") (pin "2") (pintype "passive"))
      (node (ref "R18") (pin "1") (pintype "passive"))
      (node (ref "R2") (pin "1") (pintype "passive"))
      (node (ref "R20") (pin "1") (pintype "passive"))
      (node (ref "R3") (pin "2") (pinfunction "2_2") (pintype "passive"))
      (node (ref "R34") (pin "2") (pintype "passive"))
      (node (ref "R35") (pin "2") (pintype "passive"))
      (node (ref "R36") (pin "2") (pintype "passive"))
      (node (ref "R37") (pin "2") (pintype "passive"))
      (node (ref "R38") (pin "2") (pintype "passive"))
      (node (ref "R42") (pin "1") (pintype "passive"))
      (node (ref "R6") (pin "2") (pintype "passive"))
      (node (ref "S1") (pin "1") (pinfunction "A1_1") (pintype "passive"))
      (node (ref "TF1") (pin "4") (pinfunction "VDD_4") (pintype "passive"))
      (node (ref "U1") (pin "8") (pinfunction "VCC_8") (pintype "passive"))
      (node (ref "U2") (pin "1") (pinfunction "VBAT_1") (pintype "passive"))
      (node (ref "U2") (pin "24") (pinfunction "VDD_1_24") (pintype "passive"))
      (node (ref "U2") (pin "36") (pinfunction "VDD_2_36") (pintype "passive"))
      (node (ref "U2") (pin "48") (pinfunction "VDD_3_48") (pintype "passive"))
      (node (ref "U4") (pin "2") (pinfunction "OUT_2") (pintype "passive"))
      (node (ref "U4") (pin "4") (pinfunction "OUT_4") (pintype "passive"))
      (node (ref "U5") (pin "16") (pinfunction "VCC_16") (pintype "passive"))
    )
    (net (code "75") (name "VCC5V") (class "Default")
      (node (ref "C18") (pin "2") (pintype "passive"))
      (node (ref "F1") (pin "1") (pintype "passive"))
      (node (ref "OLED") (pin "1") (pinfunction "VCC_1") (pintype "passive"))
      (node (ref "P2") (pin "4") (pinfunction "4_4") (pintype "passive"))
      (node (ref "P3") (pin "1") (pinfunction "1_1") (pintype "passive"))
      (node (ref "P4") (pin "17") (pinfunction "17_17") (pintype "passive"))
      (node (ref "P4") (pin "18") (pinfunction "18_18") (pintype "passive"))
      (node (ref "R29") (pin "2") (pintype "passive"))
      (node (ref "R40") (pin "1") (pintype "passive"))
      (node (ref "R41") (pin "1") (pintype "passive"))
      (node (ref "U3") (pin "1") (pinfunction "VCC_1") (pintype "passive"))
      (node (ref "U6") (pin "8") (pinfunction "VCC_8") (pintype "passive"))
      (node (ref "U7") (pin "1") (pinfunction "VCC_1") (pintype "passive"))
      (node (ref "U8") (pin "1") (pinfunction "VCC_1") (pintype "passive"))
    )
    (net (code "76") (name "unconnected-(TF1-DATA1-Pad8)") (class "Default")
      (node (ref "TF1") (pin "8") (pinfunction "DATA1_8") (pintype "passive"))
    )
    (net (code "77") (name "unconnected-(TF1-DATA2-Pad1)") (class "Default")
      (node (ref "TF1") (pin "1") (pinfunction "DATA2_1") (pintype "passive"))
    )
    (net (code "78") (name "unconnected-(U5-CTS#-Pad9)") (class "Default")
      (node (ref "U5") (pin "9") (pinfunction "CTS#_9") (pintype "passive"))
    )
    (net (code "79") (name "unconnected-(U5-DCD#-Pad12)") (class "Default")
      (node (ref "U5") (pin "12") (pinfunction "DCD#_12") (pintype "passive"))
    )
    (net (code "80") (name "unconnected-(U5-DSR#-Pad10)") (class "Default")
      (node (ref "U5") (pin "10") (pinfunction "DSR#_10") (pintype "passive"))
    )
    (net (code "81") (name "unconnected-(U5-DTR#-Pad13)") (class "Default")
      (node (ref "U5") (pin "13") (pinfunction "DTR#_13") (pintype "passive"))
    )
    (net (code "82") (name "unconnected-(U5-R232-Pad15)") (class "Default")
      (node (ref "U5") (pin "15") (pinfunction "R232_15") (pintype "passive"))
    )
    (net (code "83") (name "unconnected-(U5-RI#-Pad11)") (class "Default")
      (node (ref "U5") (pin "11") (pinfunction "RI#_11") (pintype "passive"))
    )
    (net (code "84") (name "unconnected-(U5-RTS#-Pad14)") (class "Default")
      (node (ref "U5") (pin "14") (pinfunction "RTS#_14") (pintype "passive"))
    )
  )
)
